# AGC-Amplifier-LM13600-Mono.net
KiCad netlist of a schematic drawn in EAGLE
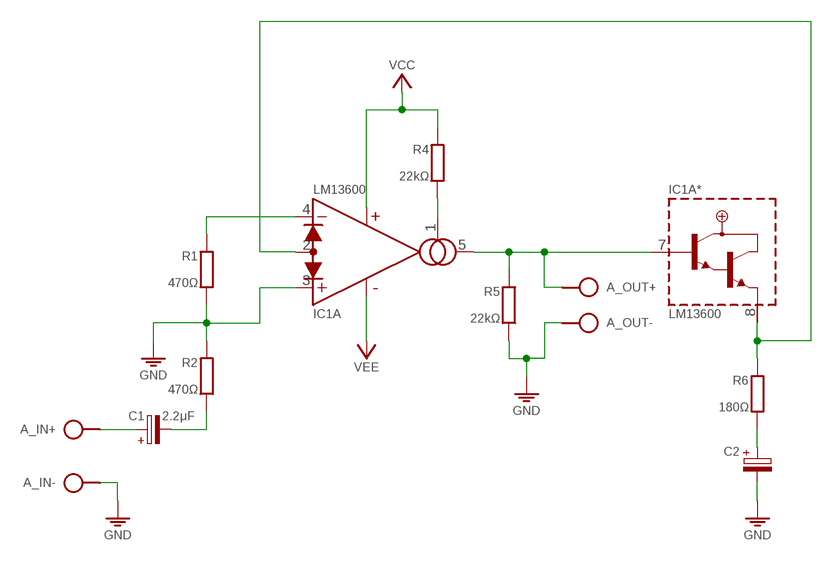
[diagram p0: schematic, sheet 1]

(export (version "E")
  (design (tool "Eeschema 10.0.6"))
  (components
    (comp (ref "A_IN")
      (value "SPAD+-+-")
      (footprint "eagle-import:SPAD+-")
      (libsource (lib "eagle-import") (part "SPAD+-+-"))
    )
    (comp (ref "A_OUT")
      (value "SPAD+-+-")
      (footprint "eagle-import:SPAD+-")
      (libsource (lib "eagle-import") (part "SPAD+-+-"))
    )
    (comp (ref "C1")
      (value "2.2μF")
      (footprint "eagle-import:E2.5-4_V")
      (libsource (lib "eagle-import") (part "CPOL-HE2,5-4/V"))
    )
    (comp (ref "C2")
      (value "CPOLE2,5-4/V")
      (footprint "eagle-import:E2.5-4_V")
      (libsource (lib "eagle-import") (part "CPOLE2,5-4/V"))
    )
    (comp (ref "IC1")
      (value "LM13600")
      (footprint "eagle-import:DIL16")
      (libsource (lib "eagle-import") (part "LM13600"))
    )
    (comp (ref "PWR")
      (value "VCC_GND_VEEPWR-+GND-")
      (footprint "eagle-import:SPAD-PWR-+GND-")
      (libsource (lib "eagle-import") (part "VCC_GND_VEEPWR-+GND-"))
    )
    (comp (ref "R1")
      (value "470Ω")
      (footprint "eagle-import:0202_7")
      (libsource (lib "eagle-import") (part "R0202/7"))
    )
    (comp (ref "R2")
      (value "470Ω")
      (footprint "eagle-import:0202_7-V")
      (libsource (lib "eagle-import") (part "R0202/7-V"))
    )
    (comp (ref "R4")
      (value "22kΩ")
      (footprint "eagle-import:0202_7")
      (libsource (lib "eagle-import") (part "R0202/7"))
    )
    (comp (ref "R5")
      (value "22kΩ")
      (footprint "eagle-import:0202_7-V")
      (libsource (lib "eagle-import") (part "R0202/7-V"))
    )
    (comp (ref "R6")
      (value "180Ω")
      (footprint "eagle-import:0202_7")
      (libsource (lib "eagle-import") (part "R0202/7"))
    )
  )
  (nets
    (net (code "1") (name "GND") (class "Default")
      (node (ref "A_IN") (pin "1") (pinfunction "P$1_1") (pintype "passive"))
      (node (ref "A_OUT") (pin "1") (pinfunction "P$1_1") (pintype "passive"))
      (node (ref "C2") (pin "-") (pinfunction "-_-") (pintype "passive"))
      (node (ref "IC1") (pin "3") (pinfunction "+IN_3") (pintype "input"))
      (node (ref "PWR") (pin "GND") (pinfunction "GND_GND") (pintype "power_in"))
      (node (ref "R1") (pin "2") (pinfunction "2_2") (pintype "passive"))
      (node (ref "R2") (pin "1") (pinfunction "1_1") (pintype "passive"))
      (node (ref "R5") (pin "2") (pinfunction "2_2") (pintype "passive"))
    )
    (net (code "2") (name "Net-(A_INA-P$1)") (class "Default")
      (node (ref "A_IN") (pin "2") (pinfunction "P$1_2") (pintype "passive"))
      (node (ref "C1") (pin "+") (pinfunction "+_+") (pintype "passive"))
    )
    (net (code "3") (name "Net-(A_OUTA-P$1)") (class "Default")
      (node (ref "A_OUT") (pin "2") (pinfunction "P$1_2") (pintype "passive"))
      (node (ref "IC1") (pin "5") (pinfunction "OUT_5") (pintype "output"))
      (node (ref "IC1") (pin "7") (pinfunction "BUFF/IN_7") (pintype "input"))
      (node (ref "R5") (pin "1") (pinfunction "1_1") (pintype "passive"))
    )
    (net (code "4") (name "Net-(C1-Pad-)") (class "Default")
      (node (ref "C1") (pin "-") (pinfunction "-_-") (pintype "passive"))
      (node (ref "R2") (pin "2") (pinfunction "2_2") (pintype "passive"))
    )
    (net (code "5") (name "Net-(C2-Pad+)") (class "Default")
      (node (ref "C2") (pin "+") (pinfunction "+_+") (pintype "passive"))
      (node (ref "R6") (pin "2") (pinfunction "2_2") (pintype "passive"))
    )
    (net (code "6") (name "Net-(IC1A-V+)") (class "Default")
      (node (ref "IC1") (pin "11") (pinfunction "V+_11") (pintype "power_in"))
      (node (ref "PWR") (pin "VCC") (pinfunction "VCC_VCC") (pintype "power_in"))
      (node (ref "R4") (pin "1") (pinfunction "1_1") (pintype "passive"))
    )
    (net (code "7") (name "Net-(IC1A-V-)") (class "Default")
      (node (ref "IC1") (pin "6") (pinfunction "V-_6") (pintype "power_in"))
      (node (ref "PWR") (pin "VEE") (pinfunction "VEE_VEE") (pintype "power_in"))
    )
    (net (code "8") (name "Net-(IC1B--IN)") (class "Default")
      (node (ref "IC1") (pin "4") (pinfunction "-IN_4") (pintype "input"))
      (node (ref "R1") (pin "1") (pinfunction "1_1") (pintype "passive"))
    )
    (net (code "9") (name "Net-(IC1B-AMP{slash}BIAS)") (class "Default")
      (node (ref "IC1") (pin "1") (pinfunction "AMP/BIAS_1") (pintype "input"))
      (node (ref "R4") (pin "2") (pinfunction "2_2") (pintype "passive"))
    )
    (net (code "10") (name "Net-(IC1B-DIODE{slash}BIAS)") (class "Default")
      (node (ref "IC1") (pin "2") (pinfunction "DIODE/BIAS_2") (pintype "input"))
      (node (ref "IC1") (pin "8") (pinfunction "BUFF/OUT_8") (pintype "output"))
      (node (ref "R6") (pin "1") (pinfunction "1_1") (pintype "passive"))
    )
  )
)
